# SparkX_smol_Dynamic_NFC_RFID_Tag.net
KiCad netlist of a schematic drawn in EAGLE
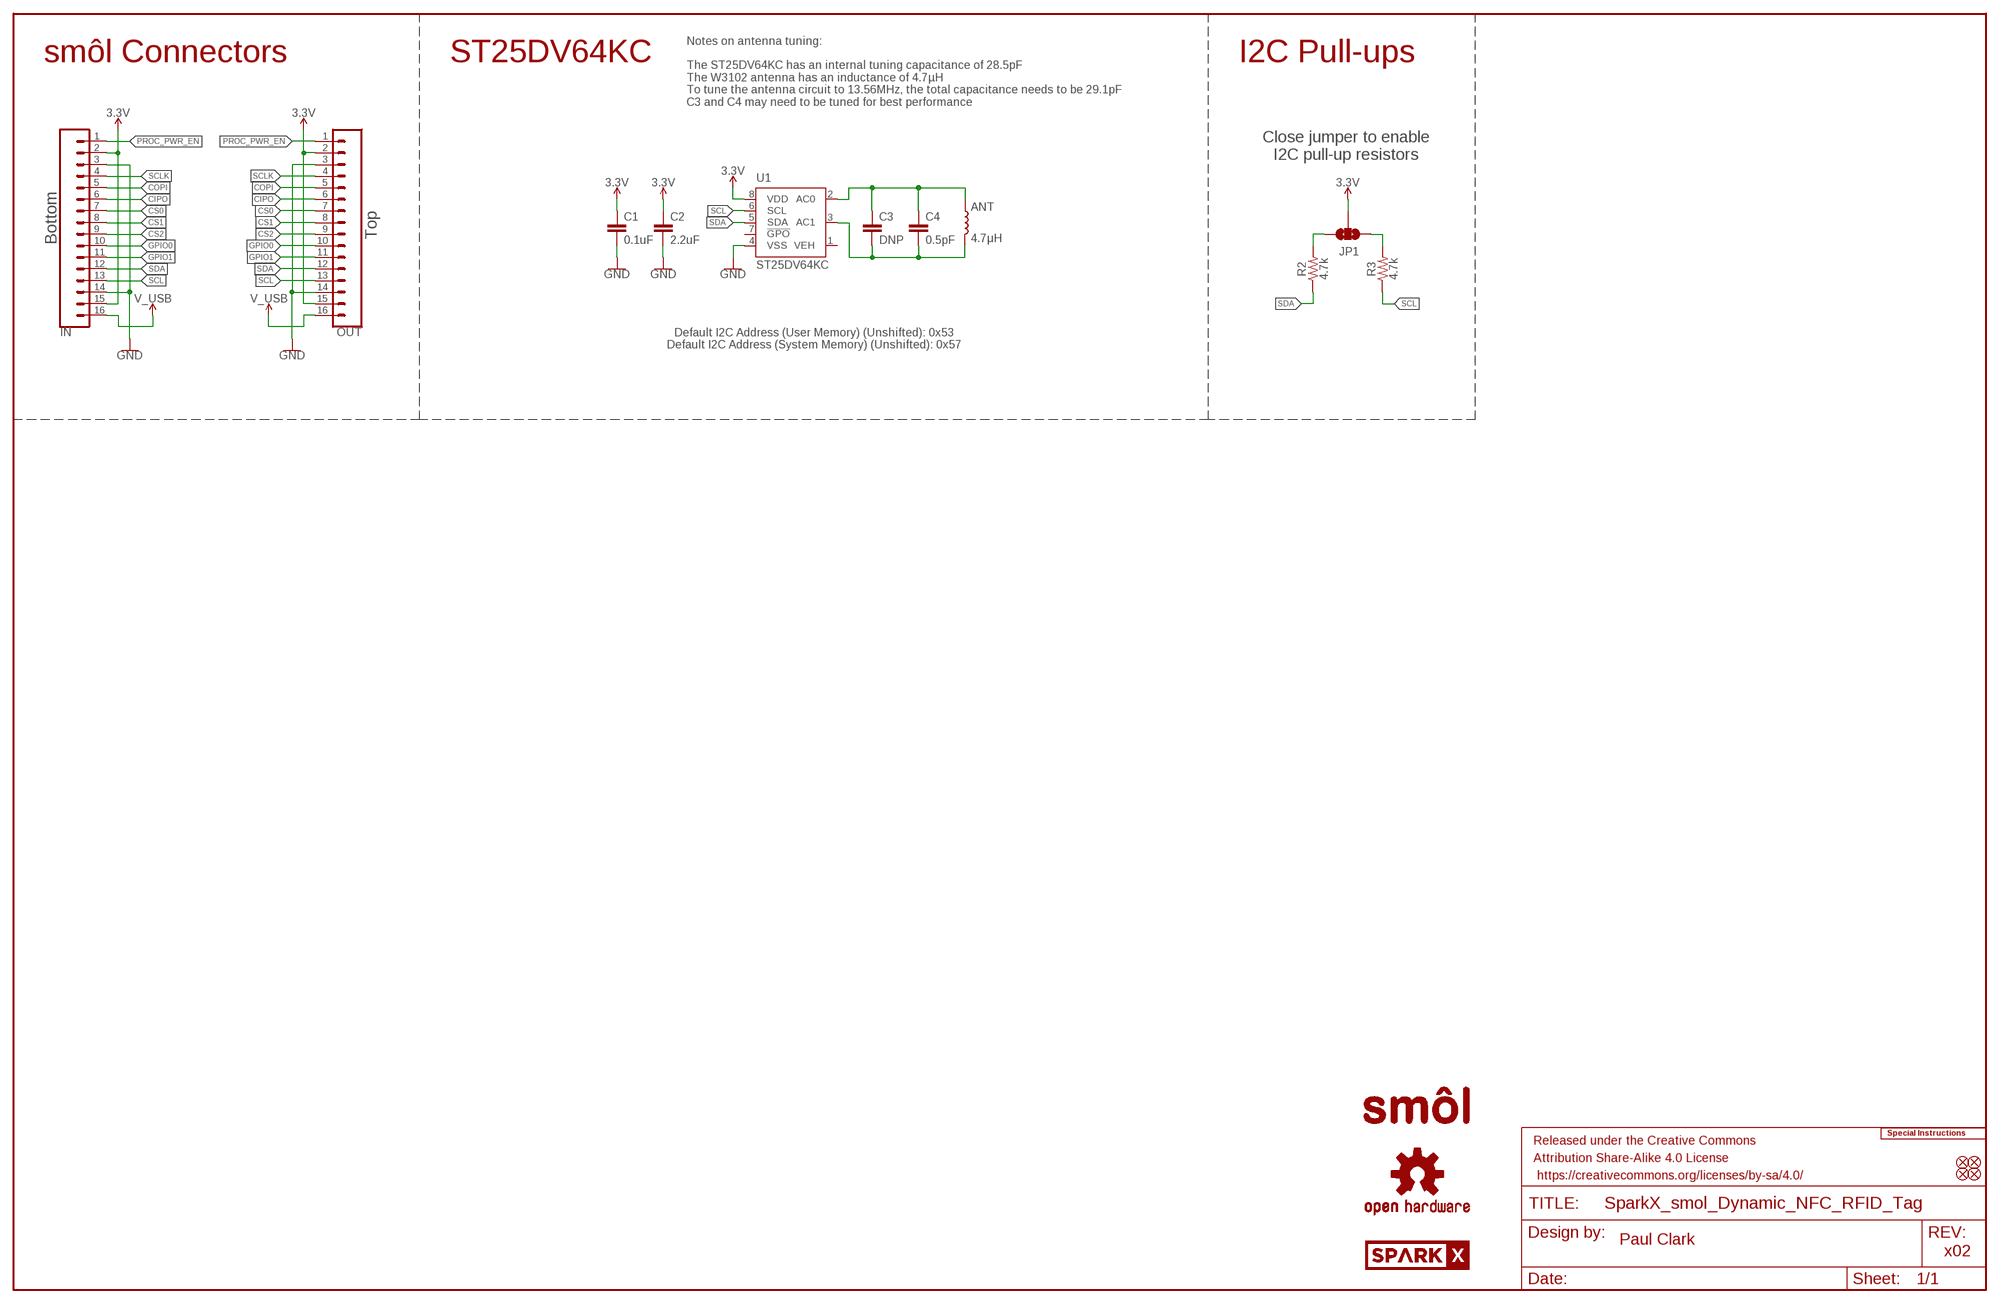
[diagram p0: schematic, sheet 1]

(export (version "E")
  (design (tool "Eeschema 10.0.6"))
  (components
    (comp (ref "ANT")
      (value "4.7μH")
      (footprint "eagle-import:W3102")
      (libsource (lib "eagle-import") (part "RFID_ANTENNA_W3102"))
    )
    (comp (ref "C1")
      (value "0.1uF")
      (footprint "eagle-import:0402-TIGHT")
      (libsource (lib "eagle-import") (part "0.1UF-0402T-6.3V-10%-X7R"))
    )
    (comp (ref "C2")
      (value "2.2uF")
      (footprint "eagle-import:0402-TIGHT")
      (libsource (lib "eagle-import") (part "2.2UF-0402_TIGHT-10V-10%-X5R"))
    )
    (comp (ref "C3")
      (value "DNP")
      (footprint "eagle-import:0402-TIGHT_NO_CREAM")
      (libsource (lib "eagle-import") (part "DNP-0402-TIGHT_NO_CREAM"))
    )
    (comp (ref "C4")
      (value "0.5pF")
      (footprint "eagle-import:0402-TIGHT")
      (libsource (lib "eagle-import") (part "0.5PF-0402_TIGHT-50V-PM0.05PF-NP0"))
    )
    (comp (ref "FD1")
      (value "FIDUCIALUFIDUCIAL")
      (footprint "eagle-import:FIDUCIAL-MICRO")
      (libsource (lib "eagle-import") (part "FIDUCIALUFIDUCIAL"))
    )
    (comp (ref "FD2")
      (value "FIDUCIALUFIDUCIAL")
      (footprint "eagle-import:FIDUCIAL-MICRO")
      (libsource (lib "eagle-import") (part "FIDUCIALUFIDUCIAL"))
    )
    (comp (ref "FD3")
      (value "FIDUCIALUFIDUCIAL")
      (footprint "eagle-import:FIDUCIAL-MICRO")
      (libsource (lib "eagle-import") (part "FIDUCIALUFIDUCIAL"))
    )
    (comp (ref "FD4")
      (value "FIDUCIALUFIDUCIAL")
      (footprint "eagle-import:FIDUCIAL-MICRO")
      (libsource (lib "eagle-import") (part "FIDUCIALUFIDUCIAL"))
    )
    (comp (ref "FRAME1")
      (value "FRAME-LEDGER")
      (footprint "eagle-import:CREATIVE_COMMONS")
      (libsource (lib "eagle-import") (part "FRAME-LEDGER"))
    )
    (comp (ref "IN")
      (value "CONN_16FPC_16_0.5MM")
      (footprint "eagle-import:FPC_16_0.5MM")
      (libsource (lib "eagle-import") (part "CONN_16FPC_16_0.5MM"))
    )
    (comp (ref "JP1")
      (value "JUMPER-SMT_3_NO_SILK")
      (footprint "eagle-import:SMT-JUMPER_3_NO_SILK")
      (libsource (lib "eagle-import") (part "JUMPER-SMT_3_NO_SILK"))
    )
    (comp (ref "LOGO1")
      (value "SPECIAL_INSTRUCTIONS-ORDERING")
      (footprint "eagle-import:ORDERING_INSTRUCTIONS")
      (libsource (lib "eagle-import") (part "SPECIAL_INSTRUCTIONS-ORDERING"))
    )
    (comp (ref "LOGO2")
      (value "OSHW-LOGOMINI")
      (footprint "eagle-import:OSHW-LOGO-MINI")
      (libsource (lib "eagle-import") (part "OSHW-LOGOMINI"))
    )
    (comp (ref "LOGO3")
      (value "OSHW-LOGOMINI")
      (footprint "eagle-import:OSHW-LOGO-MINI")
      (libsource (lib "eagle-import") (part "OSHW-LOGOMINI"))
    )
    (comp (ref "OUT")
      (value "CONN_16FPC_16_0.5MM")
      (footprint "eagle-import:FPC_16_0.5MM")
      (libsource (lib "eagle-import") (part "CONN_16FPC_16_0.5MM"))
    )
    (comp (ref "R2")
      (value "4.7k")
      (footprint "eagle-import:0402-TIGHT")
      (libsource (lib "eagle-import") (part "4.7KOHM-0402T-1/16W-1%"))
    )
    (comp (ref "R3")
      (value "4.7k")
      (footprint "eagle-import:0402-TIGHT")
      (libsource (lib "eagle-import") (part "4.7KOHM-0402T-1/16W-1%"))
    )
    (comp (ref "U$1")
      (value "SPARKX-LOGO3")
      (footprint "eagle-import:SPARKX-SMALL")
      (libsource (lib "eagle-import") (part "SPARKX-LOGO3"))
    )
    (comp (ref "U$3")
      (value "SMOL_LOGOSMALL")
      (footprint "eagle-import:SMOL_SMALL")
      (libsource (lib "eagle-import") (part "SMOL_LOGOSMALL"))
    )
    (comp (ref "U$9")
      (value "SMOL_LOGOSMALL")
      (footprint "eagle-import:SMOL_SMALL")
      (libsource (lib "eagle-import") (part "SMOL_LOGOSMALL"))
    )
    (comp (ref "U1")
      (value "ST25DV64KC")
      (footprint "eagle-import:SO08")
      (libsource (lib "eagle-import") (part "ST25DV64KC"))
    )
  )
  (nets
    (net (code "1") (name "/VEH") (class "Default")
      (node (ref "U1") (pin "1") (pinfunction "VEH_1") (pintype "power_in"))
    )
    (net (code "2") (name "3.3V") (class "Default")
      (node (ref "C1") (pin "1") (pinfunction "1_1") (pintype "passive"))
      (node (ref "C2") (pin "1") (pinfunction "1_1") (pintype "passive"))
      (node (ref "IN") (pin "15") (pinfunction "15_15") (pintype "passive"))
      (node (ref "IN") (pin "2") (pinfunction "2_2") (pintype "passive"))
      (node (ref "JP1") (pin "2") (pinfunction "2_2") (pintype "passive"))
      (node (ref "OUT") (pin "15") (pinfunction "15_15") (pintype "passive"))
      (node (ref "OUT") (pin "2") (pinfunction "2_2") (pintype "passive"))
      (node (ref "U1") (pin "8") (pinfunction "VDD_8") (pintype "power_in"))
    )
    (net (code "3") (name "CIPO") (class "Default")
      (node (ref "IN") (pin "6") (pinfunction "6_6") (pintype "passive"))
      (node (ref "OUT") (pin "6") (pinfunction "6_6") (pintype "passive"))
    )
    (net (code "4") (name "COPI") (class "Default")
      (node (ref "IN") (pin "5") (pinfunction "5_5") (pintype "passive"))
      (node (ref "OUT") (pin "5") (pinfunction "5_5") (pintype "passive"))
    )
    (net (code "5") (name "CS0") (class "Default")
      (node (ref "IN") (pin "7") (pinfunction "7_7") (pintype "passive"))
      (node (ref "OUT") (pin "7") (pinfunction "7_7") (pintype "passive"))
    )
    (net (code "6") (name "CS1") (class "Default")
      (node (ref "IN") (pin "8") (pinfunction "8_8") (pintype "passive"))
      (node (ref "OUT") (pin "8") (pinfunction "8_8") (pintype "passive"))
    )
    (net (code "7") (name "CS2") (class "Default")
      (node (ref "IN") (pin "9") (pinfunction "9_9") (pintype "passive"))
      (node (ref "OUT") (pin "9") (pinfunction "9_9") (pintype "passive"))
    )
    (net (code "8") (name "GND") (class "Default")
      (node (ref "C1") (pin "2") (pinfunction "2_2") (pintype "passive"))
      (node (ref "C2") (pin "2") (pinfunction "2_2") (pintype "passive"))
      (node (ref "IN") (pin "14") (pinfunction "14_14") (pintype "passive"))
      (node (ref "IN") (pin "3") (pinfunction "3_3") (pintype "passive"))
      (node (ref "OUT") (pin "14") (pinfunction "14_14") (pintype "passive"))
      (node (ref "OUT") (pin "3") (pinfunction "3_3") (pintype "passive"))
      (node (ref "U1") (pin "4") (pinfunction "VSS_4") (pintype "power_in"))
    )
    (net (code "9") (name "GPIO0") (class "Default")
      (node (ref "IN") (pin "10") (pinfunction "10_10") (pintype "passive"))
      (node (ref "OUT") (pin "10") (pinfunction "10_10") (pintype "passive"))
    )
    (net (code "10") (name "GPIO1") (class "Default")
      (node (ref "IN") (pin "11") (pinfunction "11_11") (pintype "passive"))
      (node (ref "OUT") (pin "11") (pinfunction "11_11") (pintype "passive"))
    )
    (net (code "11") (name "Net-(JP1-Pad1)") (class "Default")
      (node (ref "JP1") (pin "1") (pinfunction "1_1") (pintype "passive"))
      (node (ref "R3") (pin "2") (pinfunction "2_2") (pintype "passive"))
    )
    (net (code "12") (name "Net-(JP1-Pad3)") (class "Default")
      (node (ref "JP1") (pin "3") (pinfunction "3_3") (pintype "passive"))
      (node (ref "R2") (pin "2") (pinfunction "2_2") (pintype "passive"))
    )
    (net (code "13") (name "Net-(U1-AC0)") (class "Default")
      (node (ref "ANT") (pin "1") (pinfunction "1_1") (pintype "passive"))
      (node (ref "C3") (pin "1") (pinfunction "1_1") (pintype "passive"))
      (node (ref "C4") (pin "1") (pinfunction "1_1") (pintype "passive"))
      (node (ref "U1") (pin "2") (pinfunction "AC0_2") (pintype "bidirectional"))
    )
    (net (code "14") (name "Net-(U1-AC1)") (class "Default")
      (node (ref "ANT") (pin "2") (pinfunction "2_2") (pintype "passive"))
      (node (ref "C3") (pin "2") (pinfunction "2_2") (pintype "passive"))
      (node (ref "C4") (pin "2") (pinfunction "2_2") (pintype "passive"))
      (node (ref "U1") (pin "3") (pinfunction "AC1_3") (pintype "bidirectional"))
    )
    (net (code "15") (name "PROC_PWR_EN") (class "Default")
      (node (ref "IN") (pin "1") (pinfunction "1_1") (pintype "passive"))
      (node (ref "OUT") (pin "1") (pinfunction "1_1") (pintype "passive"))
    )
    (net (code "16") (name "SCL") (class "Default")
      (node (ref "IN") (pin "13") (pinfunction "13_13") (pintype "passive"))
      (node (ref "OUT") (pin "13") (pinfunction "13_13") (pintype "passive"))
      (node (ref "R3") (pin "1") (pinfunction "1_1") (pintype "passive"))
      (node (ref "U1") (pin "6") (pinfunction "SCL_6") (pintype "bidirectional"))
    )
    (net (code "17") (name "SCLK") (class "Default")
      (node (ref "IN") (pin "4") (pinfunction "4_4") (pintype "passive"))
      (node (ref "OUT") (pin "4") (pinfunction "4_4") (pintype "passive"))
    )
    (net (code "18") (name "SDA") (class "Default")
      (node (ref "IN") (pin "12") (pinfunction "12_12") (pintype "passive"))
      (node (ref "OUT") (pin "12") (pinfunction "12_12") (pintype "passive"))
      (node (ref "R2") (pin "1") (pinfunction "1_1") (pintype "passive"))
      (node (ref "U1") (pin "5") (pinfunction "SDA_5") (pintype "bidirectional"))
    )
    (net (code "19") (name "V_USB") (class "Default")
      (node (ref "IN") (pin "16") (pinfunction "16_16") (pintype "passive"))
      (node (ref "OUT") (pin "16") (pinfunction "16_16") (pintype "passive"))
    )
    (net (code "20") (name "unconnected-(U1-~{GPO}-Pad7)") (class "Default")
      (node (ref "U1") (pin "7") (pinfunction "~{GPO}_7") (pintype "output"))
    )
  )
)
